# ATMega2650.net
KiCad netlist of a schematic drawn in Altium Designer
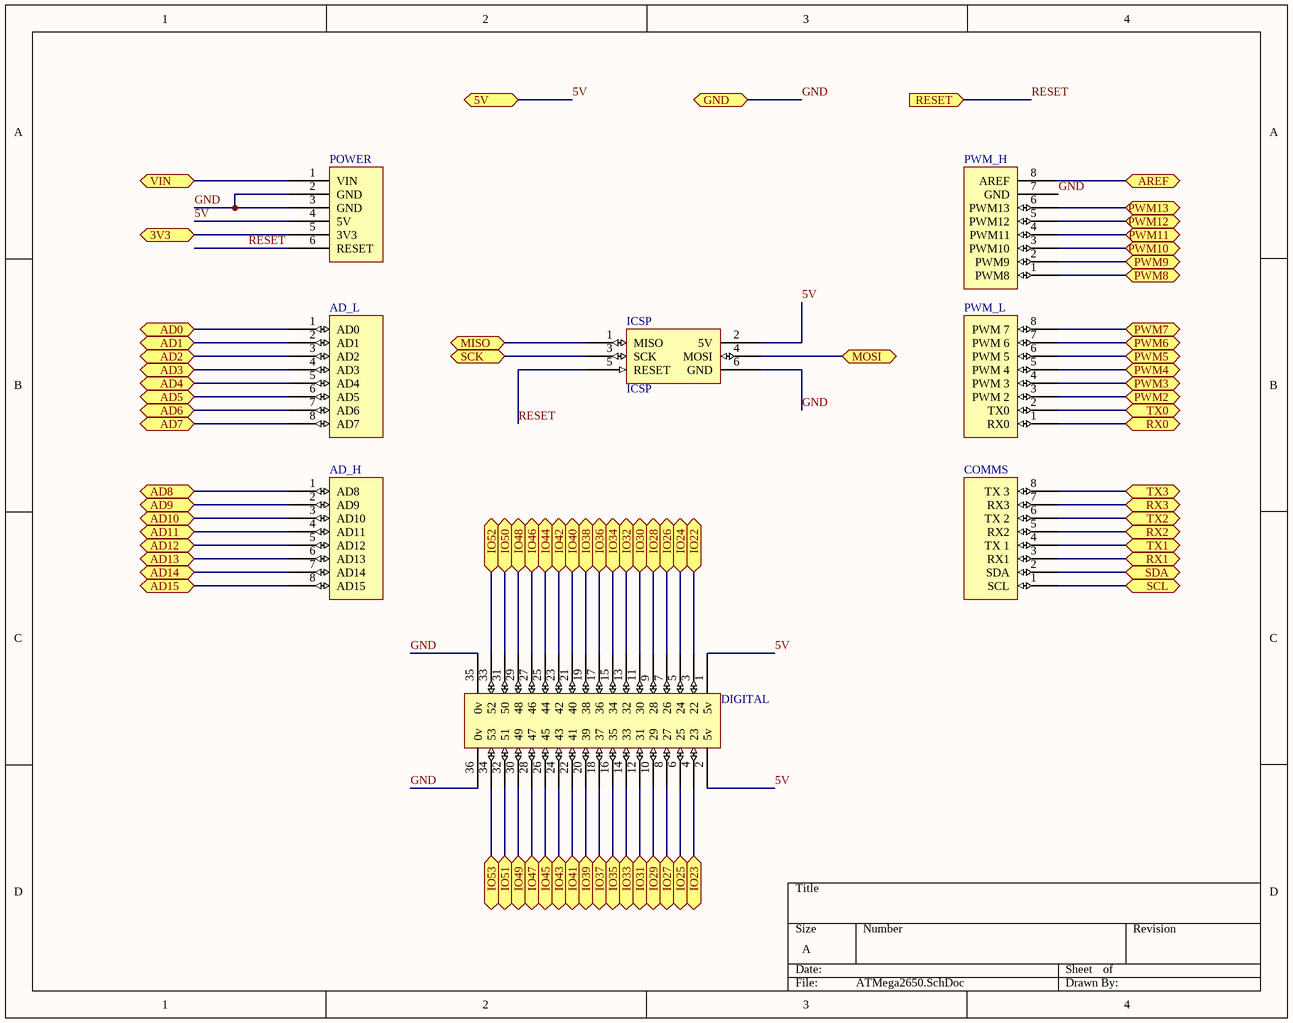
[diagram p0: ATMega2650.SchDoc]

(export (version "E")
  (design (tool "Eeschema 10.0.6"))
  (components
    (comp (ref "AD_H") (value "AD_H") (footprint "Header 8x1 8.5mm") (libsource (lib "Header") (part "AD_H")))
    (comp (ref "AD_L") (value "AD_L") (footprint "Header 8x1 8.5mm") (libsource (lib "Header") (part "AD_L")))
    (comp (ref "COMMS")
      (value "Communication")
      (footprint "Header 8x1 8.5mm")
      (libsource (lib "Header") (part "Communication"))
    )
    (comp (ref "DIGITAL")
      (value "IO_36")
      (footprint "HEADER 36X 8MM")
      (libsource (lib "Header") (part "IO_36"))
    )
    (comp (ref "ICSP") (value "ICSP") (footprint "ICSP") (libsource (lib "Header") (part "ICSP")))
    (comp (ref "POWER")
      (value "POWER")
      (footprint "Header 6x1 8.5mm")
      (libsource (lib "Header") (part "POWER"))
    )
    (comp (ref "PWM_H")
      (value "PWM_H")
      (footprint "Header 8x1 8.5mm")
      (libsource (lib "Header") (part "PWM_H"))
    )
    (comp (ref "PWM_L")
      (value "PWM_L")
      (footprint "Header 8x1 8.5mm")
      (libsource (lib "Header") (part "PWM_L"))
    )
  )
  (nets
    (net (code "1") (name "/3V3") (class "Default")
      (node (ref "POWER") (pin "5") (pinfunction "3V3_5") (pintype "power_in"))
    )
    (net (code "2") (name "/5V") (class "Default")
      (node (ref "DIGITAL") (pin "1") (pinfunction "5v_1") (pintype "power_in"))
      (node (ref "DIGITAL") (pin "2") (pinfunction "5v_2") (pintype "power_in"))
      (node (ref "ICSP") (pin "2") (pinfunction "5V_2") (pintype "power_in"))
      (node (ref "POWER") (pin "4") (pinfunction "5V_4") (pintype "power_in"))
    )
    (net (code "3") (name "/AD0") (class "Default")
      (node (ref "AD_L") (pin "1") (pinfunction "AD0_1") (pintype "bidirectional"))
    )
    (net (code "4") (name "/AD1") (class "Default")
      (node (ref "AD_L") (pin "2") (pinfunction "AD1_2") (pintype "bidirectional"))
    )
    (net (code "5") (name "/AD2") (class "Default")
      (node (ref "AD_L") (pin "3") (pinfunction "AD2_3") (pintype "bidirectional"))
    )
    (net (code "6") (name "/AD3") (class "Default")
      (node (ref "AD_L") (pin "4") (pinfunction "AD3_4") (pintype "bidirectional"))
    )
    (net (code "7") (name "/AD4") (class "Default")
      (node (ref "AD_L") (pin "5") (pinfunction "AD4_5") (pintype "bidirectional"))
    )
    (net (code "8") (name "/AD5") (class "Default")
      (node (ref "AD_L") (pin "6") (pinfunction "AD5_6") (pintype "bidirectional"))
    )
    (net (code "9") (name "/AD6") (class "Default")
      (node (ref "AD_L") (pin "7") (pinfunction "AD6_7") (pintype "bidirectional"))
    )
    (net (code "10") (name "/AD7") (class "Default")
      (node (ref "AD_L") (pin "8") (pinfunction "AD7_8") (pintype "bidirectional"))
    )
    (net (code "11") (name "/AD8") (class "Default")
      (node (ref "AD_H") (pin "1") (pinfunction "AD8_1") (pintype "bidirectional"))
    )
    (net (code "12") (name "/AD9") (class "Default")
      (node (ref "AD_H") (pin "2") (pinfunction "AD9_2") (pintype "bidirectional"))
    )
    (net (code "13") (name "/AD10") (class "Default")
      (node (ref "AD_H") (pin "3") (pinfunction "AD10_3") (pintype "bidirectional"))
    )
    (net (code "14") (name "/AD11") (class "Default")
      (node (ref "AD_H") (pin "4") (pinfunction "AD11_4") (pintype "bidirectional"))
    )
    (net (code "15") (name "/AD12") (class "Default")
      (node (ref "AD_H") (pin "5") (pinfunction "AD12_5") (pintype "bidirectional"))
    )
    (net (code "16") (name "/AD13") (class "Default")
      (node (ref "AD_H") (pin "6") (pinfunction "AD13_6") (pintype "bidirectional"))
    )
    (net (code "17") (name "/AD14") (class "Default")
      (node (ref "AD_H") (pin "7") (pinfunction "AD14_7") (pintype "bidirectional"))
    )
    (net (code "18") (name "/AD15") (class "Default")
      (node (ref "AD_H") (pin "8") (pinfunction "AD15_8") (pintype "bidirectional"))
    )
    (net (code "19") (name "/AREF") (class "Default")
      (node (ref "PWM_H") (pin "8") (pinfunction "AREF_8") (pintype "passive"))
    )
    (net (code "20") (name "/GND") (class "Default")
      (node (ref "DIGITAL") (pin "35") (pinfunction "0v_35") (pintype "power_in"))
      (node (ref "DIGITAL") (pin "36") (pinfunction "0v_36") (pintype "power_in"))
      (node (ref "ICSP") (pin "6") (pinfunction "GND_6") (pintype "power_in"))
      (node (ref "POWER") (pin "2") (pinfunction "GND_2") (pintype "power_in"))
      (node (ref "POWER") (pin "3") (pinfunction "GND_3") (pintype "power_in"))
      (node (ref "PWM_H") (pin "7") (pinfunction "GND_7") (pintype "power_in"))
    )
    (net (code "21") (name "/IO22") (class "Default")
      (node (ref "DIGITAL") (pin "3") (pinfunction "22_3") (pintype "bidirectional"))
    )
    (net (code "22") (name "/IO23") (class "Default")
      (node (ref "DIGITAL") (pin "4") (pinfunction "23_4") (pintype "bidirectional"))
    )
    (net (code "23") (name "/IO24") (class "Default")
      (node (ref "DIGITAL") (pin "5") (pinfunction "24_5") (pintype "bidirectional"))
    )
    (net (code "24") (name "/IO25") (class "Default")
      (node (ref "DIGITAL") (pin "6") (pinfunction "25_6") (pintype "bidirectional"))
    )
    (net (code "25") (name "/IO26") (class "Default")
      (node (ref "DIGITAL") (pin "7") (pinfunction "26_7") (pintype "bidirectional"))
    )
    (net (code "26") (name "/IO27") (class "Default")
      (node (ref "DIGITAL") (pin "8") (pinfunction "27_8") (pintype "bidirectional"))
    )
    (net (code "27") (name "/IO28") (class "Default")
      (node (ref "DIGITAL") (pin "9") (pinfunction "28_9") (pintype "bidirectional"))
    )
    (net (code "28") (name "/IO29") (class "Default")
      (node (ref "DIGITAL") (pin "10") (pinfunction "29_10") (pintype "bidirectional"))
    )
    (net (code "29") (name "/IO30") (class "Default")
      (node (ref "DIGITAL") (pin "11") (pinfunction "30_11") (pintype "bidirectional"))
    )
    (net (code "30") (name "/IO31") (class "Default")
      (node (ref "DIGITAL") (pin "12") (pinfunction "31_12") (pintype "bidirectional"))
    )
    (net (code "31") (name "/IO32") (class "Default")
      (node (ref "DIGITAL") (pin "13") (pinfunction "32_13") (pintype "bidirectional"))
    )
    (net (code "32") (name "/IO33") (class "Default")
      (node (ref "DIGITAL") (pin "14") (pinfunction "33_14") (pintype "bidirectional"))
    )
    (net (code "33") (name "/IO34") (class "Default")
      (node (ref "DIGITAL") (pin "15") (pinfunction "34_15") (pintype "bidirectional"))
    )
    (net (code "34") (name "/IO35") (class "Default")
      (node (ref "DIGITAL") (pin "16") (pinfunction "35_16") (pintype "bidirectional"))
    )
    (net (code "35") (name "/IO36") (class "Default")
      (node (ref "DIGITAL") (pin "17") (pinfunction "36_17") (pintype "bidirectional"))
    )
    (net (code "36") (name "/IO37") (class "Default")
      (node (ref "DIGITAL") (pin "18") (pinfunction "37_18") (pintype "bidirectional"))
    )
    (net (code "37") (name "/IO38") (class "Default")
      (node (ref "DIGITAL") (pin "19") (pinfunction "38_19") (pintype "bidirectional"))
    )
    (net (code "38") (name "/IO39") (class "Default")
      (node (ref "DIGITAL") (pin "20") (pinfunction "39_20") (pintype "bidirectional"))
    )
    (net (code "39") (name "/IO40") (class "Default")
      (node (ref "DIGITAL") (pin "21") (pinfunction "40_21") (pintype "bidirectional"))
    )
    (net (code "40") (name "/IO41") (class "Default")
      (node (ref "DIGITAL") (pin "22") (pinfunction "41_22") (pintype "bidirectional"))
    )
    (net (code "41") (name "/IO42") (class "Default")
      (node (ref "DIGITAL") (pin "23") (pinfunction "42_23") (pintype "bidirectional"))
    )
    (net (code "42") (name "/IO43") (class "Default")
      (node (ref "DIGITAL") (pin "24") (pinfunction "43_24") (pintype "bidirectional"))
    )
    (net (code "43") (name "/IO44") (class "Default")
      (node (ref "DIGITAL") (pin "25") (pinfunction "44_25") (pintype "bidirectional"))
    )
    (net (code "44") (name "/IO45") (class "Default")
      (node (ref "DIGITAL") (pin "26") (pinfunction "45_26") (pintype "bidirectional"))
    )
    (net (code "45") (name "/IO46") (class "Default")
      (node (ref "DIGITAL") (pin "27") (pinfunction "46_27") (pintype "bidirectional"))
    )
    (net (code "46") (name "/IO47") (class "Default")
      (node (ref "DIGITAL") (pin "28") (pinfunction "47_28") (pintype "bidirectional"))
    )
    (net (code "47") (name "/IO48") (class "Default")
      (node (ref "DIGITAL") (pin "29") (pinfunction "48_29") (pintype "bidirectional"))
    )
    (net (code "48") (name "/IO49") (class "Default")
      (node (ref "DIGITAL") (pin "30") (pinfunction "49_30") (pintype "bidirectional"))
    )
    (net (code "49") (name "/IO50") (class "Default")
      (node (ref "DIGITAL") (pin "31") (pinfunction "50_31") (pintype "bidirectional"))
    )
    (net (code "50") (name "/IO51") (class "Default")
      (node (ref "DIGITAL") (pin "32") (pinfunction "51_32") (pintype "bidirectional"))
    )
    (net (code "51") (name "/IO52") (class "Default")
      (node (ref "DIGITAL") (pin "33") (pinfunction "52_33") (pintype "bidirectional"))
    )
    (net (code "52") (name "/IO53") (class "Default")
      (node (ref "DIGITAL") (pin "34") (pinfunction "53_34") (pintype "bidirectional"))
    )
    (net (code "53") (name "/MISO") (class "Default")
      (node (ref "ICSP") (pin "1") (pinfunction "MISO_1") (pintype "bidirectional"))
    )
    (net (code "54") (name "/MOSI") (class "Default")
      (node (ref "ICSP") (pin "4") (pinfunction "MOSI_4") (pintype "bidirectional"))
    )
    (net (code "55") (name "/PWM2") (class "Default")
      (node (ref "PWM_L") (pin "3") (pinfunction "PWM_2_3") (pintype "bidirectional"))
    )
    (net (code "56") (name "/PWM3") (class "Default")
      (node (ref "PWM_L") (pin "4") (pinfunction "PWM_3_4") (pintype "bidirectional"))
    )
    (net (code "57") (name "/PWM4") (class "Default")
      (node (ref "PWM_L") (pin "5") (pinfunction "PWM_4_5") (pintype "bidirectional"))
    )
    (net (code "58") (name "/PWM5") (class "Default")
      (node (ref "PWM_L") (pin "6") (pinfunction "PWM_5_6") (pintype "bidirectional"))
    )
    (net (code "59") (name "/PWM6") (class "Default")
      (node (ref "PWM_L") (pin "7") (pinfunction "PWM_6_7") (pintype "bidirectional"))
    )
    (net (code "60") (name "/PWM7") (class "Default")
      (node (ref "PWM_L") (pin "8") (pinfunction "PWM_7_8") (pintype "bidirectional"))
    )
    (net (code "61") (name "/PWM8") (class "Default")
      (node (ref "PWM_H") (pin "1") (pinfunction "PWM8_1") (pintype "bidirectional"))
    )
    (net (code "62") (name "/PWM9") (class "Default")
      (node (ref "PWM_H") (pin "2") (pinfunction "PWM9_2") (pintype "bidirectional"))
    )
    (net (code "63") (name "/PWM10") (class "Default")
      (node (ref "PWM_H") (pin "3") (pinfunction "PWM10_3") (pintype "bidirectional"))
    )
    (net (code "64") (name "/PWM11") (class "Default")
      (node (ref "PWM_H") (pin "4") (pinfunction "PWM11_4") (pintype "bidirectional"))
    )
    (net (code "65") (name "/PWM12") (class "Default")
      (node (ref "PWM_H") (pin "5") (pinfunction "PWM12_5") (pintype "bidirectional"))
    )
    (net (code "66") (name "/PWM13") (class "Default")
      (node (ref "PWM_H") (pin "6") (pinfunction "PWM13_6") (pintype "bidirectional"))
    )
    (net (code "67") (name "/RESET") (class "Default")
      (node (ref "ICSP") (pin "5") (pinfunction "RESET_5") (pintype "input"))
      (node (ref "POWER") (pin "6") (pinfunction "RESET_6") (pintype "passive"))
    )
    (net (code "68") (name "/RX0") (class "Default")
      (node (ref "PWM_L") (pin "1") (pinfunction "RX0_1") (pintype "bidirectional"))
    )
    (net (code "69") (name "/RX1") (class "Default")
      (node (ref "COMMS") (pin "3") (pinfunction "RX1_3") (pintype "bidirectional"))
    )
    (net (code "70") (name "/RX2") (class "Default")
      (node (ref "COMMS") (pin "5") (pinfunction "RX2_5") (pintype "bidirectional"))
    )
    (net (code "71") (name "/RX3") (class "Default")
      (node (ref "COMMS") (pin "7") (pinfunction "RX3_7") (pintype "bidirectional"))
    )
    (net (code "72") (name "/SCK") (class "Default")
      (node (ref "ICSP") (pin "3") (pinfunction "SCK_3") (pintype "bidirectional"))
    )
    (net (code "73") (name "/SCL") (class "Default")
      (node (ref "COMMS") (pin "1") (pinfunction "SCL_1") (pintype "bidirectional"))
    )
    (net (code "74") (name "/SDA") (class "Default")
      (node (ref "COMMS") (pin "2") (pinfunction "SDA_2") (pintype "bidirectional"))
    )
    (net (code "75") (name "/TX0") (class "Default")
      (node (ref "PWM_L") (pin "2") (pinfunction "TX0_2") (pintype "bidirectional"))
    )
    (net (code "76") (name "/TX1") (class "Default")
      (node (ref "COMMS") (pin "4") (pinfunction "TX_1_4") (pintype "bidirectional"))
    )
    (net (code "77") (name "/TX2") (class "Default")
      (node (ref "COMMS") (pin "6") (pinfunction "TX_2_6") (pintype "bidirectional"))
    )
    (net (code "78") (name "/TX3") (class "Default")
      (node (ref "COMMS") (pin "8") (pinfunction "TX_3_8") (pintype "bidirectional"))
    )
    (net (code "79") (name "/VIN") (class "Default")
      (node (ref "POWER") (pin "1") (pinfunction "VIN_1") (pintype "power_in"))
    )
  )
)
